# 11Dof_MPU6050_HighAcc.net
KiCad netlist of a schematic drawn in EAGLE
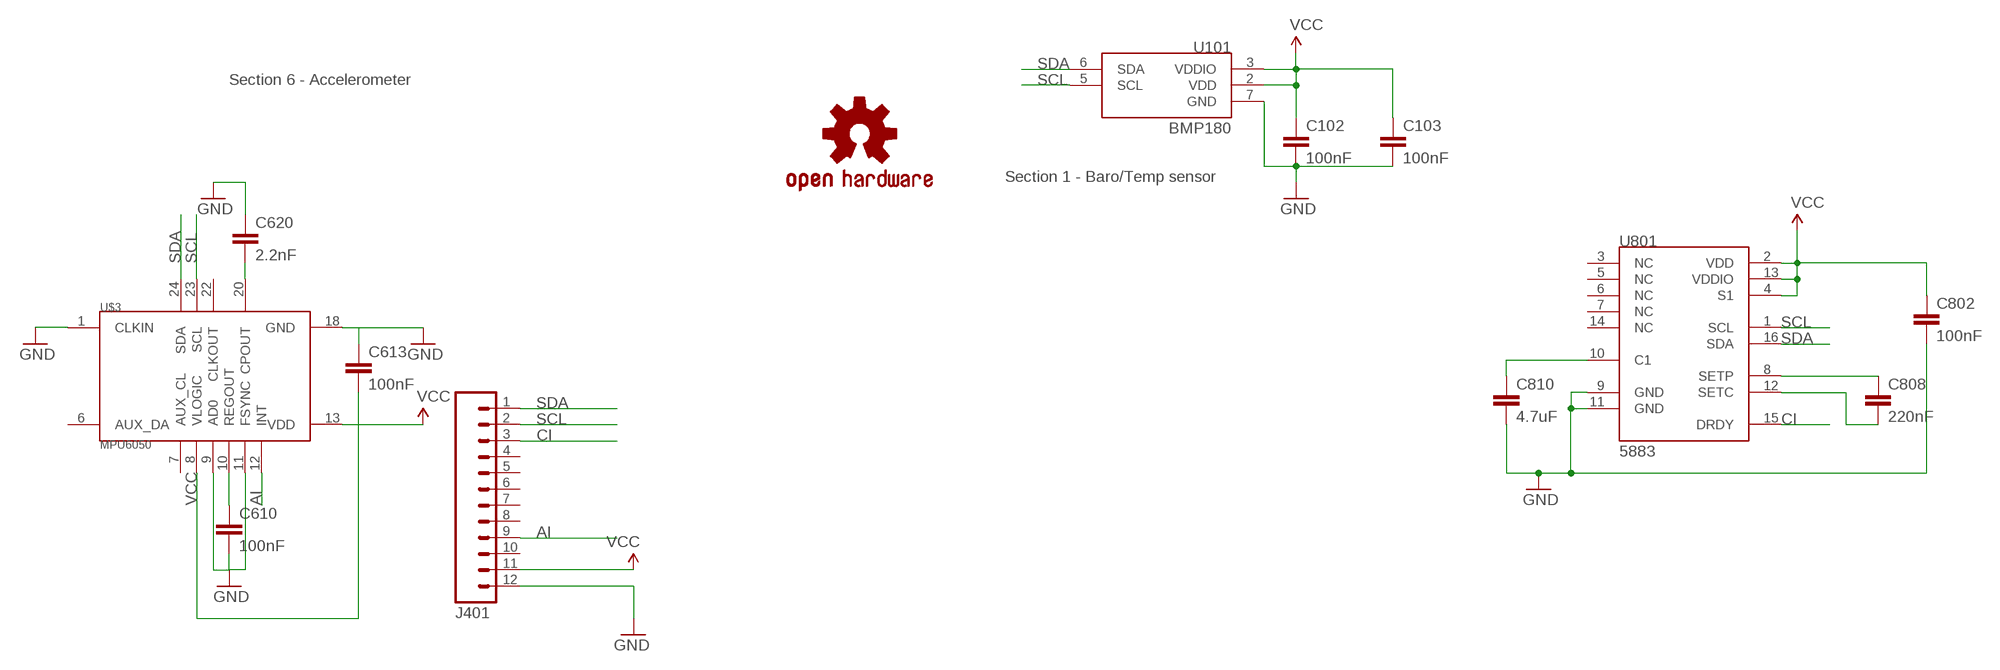
[diagram p0: schematic, sheet 1]

(export (version "E")
  (design (tool "Eeschema 10.0.6"))
  (components
    (comp (ref "C102")
      (value "100nF")
      (footprint "eagle-import:0603-CAP")
      (libsource (lib "eagle-import") (part "CAP0603-CAP"))
    )
    (comp (ref "C103")
      (value "100nF")
      (footprint "eagle-import:0603-CAP")
      (libsource (lib "eagle-import") (part "CAP0603-CAP"))
    )
    (comp (ref "C610")
      (value "100nF")
      (footprint "eagle-import:0603-CAP")
      (libsource (lib "eagle-import") (part "CAP0603-CAP"))
    )
    (comp (ref "C613")
      (value "100nF")
      (footprint "eagle-import:0603-CAP")
      (libsource (lib "eagle-import") (part "CAP0603-CAP"))
    )
    (comp (ref "C620")
      (value "2.2nF")
      (footprint "eagle-import:0603-CAP")
      (libsource (lib "eagle-import") (part "CAP0603-CAP"))
    )
    (comp (ref "C802")
      (value "100nF")
      (footprint "eagle-import:0603-CAP")
      (libsource (lib "eagle-import") (part "CAP0603-CAP"))
    )
    (comp (ref "C808")
      (value "220nF")
      (footprint "eagle-import:0603-CAP")
      (libsource (lib "eagle-import") (part "CAP0603-CAP"))
    )
    (comp (ref "C810")
      (value "4.7uF")
      (footprint "eagle-import:0603-CAP")
      (libsource (lib "eagle-import") (part "CAP0603-CAP"))
    )
    (comp (ref "J401")
      (value "M12PTH")
      (footprint "eagle-import:1X12")
      (libsource (lib "eagle-import") (part "M12PTH"))
    )
    (comp (ref "U$2")
      (value "OSHW-LOGOS")
      (footprint "eagle-import:OSHW-LOGO-S")
      (libsource (lib "eagle-import") (part "OSHW-LOGOS"))
    )
    (comp (ref "U$3")
      (value "MPU6050")
      (footprint "eagle-import:MPU60X0")
      (libsource (lib "eagle-import") (part "MPU6050"))
    )
    (comp (ref "U101")
      (value "BMP180")
      (footprint "eagle-import:BMP180")
      (libsource (lib "eagle-import") (part "BMP180"))
    )
    (comp (ref "U801")
      (value "5883")
      (footprint "eagle-import:16LPCC")
      (libsource (lib "eagle-import") (part "HMC5883LSMD"))
    )
  )
  (nets
    (net (code "1") (name "/AI") (class "Default")
      (node (ref "J401") (pin "9") (pinfunction "9_9") (pintype "passive"))
      (node (ref "U$3") (pin "12") (pinfunction "INT_12") (pintype "output"))
    )
    (net (code "2") (name "/CI") (class "Default")
      (node (ref "J401") (pin "3") (pinfunction "3_3") (pintype "passive"))
      (node (ref "U801") (pin "15") (pinfunction "DRDY_15") (pintype "bidirectional"))
    )
    (net (code "3") (name "/SCL") (class "Default")
      (node (ref "J401") (pin "2") (pinfunction "2_2") (pintype "passive"))
      (node (ref "U$3") (pin "23") (pinfunction "SCL_23") (pintype "bidirectional"))
      (node (ref "U101") (pin "5") (pinfunction "SCL_5") (pintype "input"))
      (node (ref "U801") (pin "1") (pinfunction "SCL_1") (pintype "bidirectional"))
    )
    (net (code "4") (name "/SDA") (class "Default")
      (node (ref "J401") (pin "1") (pinfunction "1_1") (pintype "passive"))
      (node (ref "U$3") (pin "24") (pinfunction "SDA_24") (pintype "bidirectional"))
      (node (ref "U101") (pin "6") (pinfunction "SDA_6") (pintype "bidirectional"))
      (node (ref "U801") (pin "16") (pinfunction "SDA_16") (pintype "bidirectional"))
    )
    (net (code "5") (name "GND") (class "Default")
      (node (ref "C102") (pin "2") (pinfunction "2_2") (pintype "passive"))
      (node (ref "C103") (pin "2") (pinfunction "2_2") (pintype "passive"))
      (node (ref "C610") (pin "2") (pinfunction "2_2") (pintype "passive"))
      (node (ref "C613") (pin "1") (pinfunction "1_1") (pintype "passive"))
      (node (ref "C620") (pin "1") (pinfunction "1_1") (pintype "passive"))
      (node (ref "C802") (pin "2") (pinfunction "2_2") (pintype "passive"))
      (node (ref "C810") (pin "2") (pinfunction "2_2") (pintype "passive"))
      (node (ref "J401") (pin "12") (pinfunction "12_12") (pintype "passive"))
      (node (ref "U$3") (pin "1") (pinfunction "CLKIN_1") (pintype "input"))
      (node (ref "U$3") (pin "11") (pinfunction "FSYNC_11") (pintype "bidirectional"))
      (node (ref "U$3") (pin "18") (pinfunction "GND_18") (pintype "power_in"))
      (node (ref "U$3") (pin "9") (pinfunction "AD0_9") (pintype "output"))
      (node (ref "U101") (pin "7") (pinfunction "GND_7") (pintype "power_in"))
      (node (ref "U801") (pin "11") (pinfunction "GND_11") (pintype "bidirectional"))
      (node (ref "U801") (pin "9") (pinfunction "GND_9") (pintype "bidirectional"))
    )
    (net (code "6") (name "Net-(U$3-CPOUT)") (class "Default")
      (node (ref "C620") (pin "2") (pinfunction "2_2") (pintype "passive"))
      (node (ref "U$3") (pin "20") (pinfunction "CPOUT_20") (pintype "output"))
    )
    (net (code "7") (name "Net-(U$3-REGOUT)") (class "Default")
      (node (ref "C610") (pin "1") (pinfunction "1_1") (pintype "passive"))
      (node (ref "U$3") (pin "10") (pinfunction "REGOUT_10") (pintype "bidirectional"))
    )
    (net (code "8") (name "Net-(U801-C1)") (class "Default")
      (node (ref "C810") (pin "1") (pinfunction "1_1") (pintype "passive"))
      (node (ref "U801") (pin "10") (pinfunction "C1_10") (pintype "bidirectional"))
    )
    (net (code "9") (name "Net-(U801-SETC)") (class "Default")
      (node (ref "C808") (pin "2") (pinfunction "2_2") (pintype "passive"))
      (node (ref "U801") (pin "12") (pinfunction "SETC_12") (pintype "bidirectional"))
    )
    (net (code "10") (name "Net-(U801-SETP)") (class "Default")
      (node (ref "C808") (pin "1") (pinfunction "1_1") (pintype "passive"))
      (node (ref "U801") (pin "8") (pinfunction "SETP_8") (pintype "bidirectional"))
    )
    (net (code "11") (name "VCC") (class "Default")
      (node (ref "C102") (pin "1") (pinfunction "1_1") (pintype "passive"))
      (node (ref "C103") (pin "1") (pinfunction "1_1") (pintype "passive"))
      (node (ref "C613") (pin "2") (pinfunction "2_2") (pintype "passive"))
      (node (ref "C802") (pin "1") (pinfunction "1_1") (pintype "passive"))
      (node (ref "J401") (pin "11") (pinfunction "11_11") (pintype "passive"))
      (node (ref "U$3") (pin "13") (pinfunction "VDD_13") (pintype "power_in"))
      (node (ref "U$3") (pin "8") (pinfunction "VLOGIC_8") (pintype "bidirectional"))
      (node (ref "U101") (pin "2") (pinfunction "VDD_2") (pintype "power_in"))
      (node (ref "U101") (pin "3") (pinfunction "VDDIO_3") (pintype "power_in"))
      (node (ref "U801") (pin "13") (pinfunction "VDDIO_13") (pintype "bidirectional"))
      (node (ref "U801") (pin "2") (pinfunction "VDD_2") (pintype "bidirectional"))
      (node (ref "U801") (pin "4") (pinfunction "S1_4") (pintype "bidirectional"))
    )
    (net (code "12") (name "unconnected-(J401-Pad4)") (class "Default")
      (node (ref "J401") (pin "4") (pinfunction "4_4") (pintype "passive"))
    )
    (net (code "13") (name "unconnected-(J401-Pad5)") (class "Default")
      (node (ref "J401") (pin "5") (pinfunction "5_5") (pintype "passive"))
    )
    (net (code "14") (name "unconnected-(J401-Pad6)") (class "Default")
      (node (ref "J401") (pin "6") (pinfunction "6_6") (pintype "passive"))
    )
    (net (code "15") (name "unconnected-(J401-Pad7)") (class "Default")
      (node (ref "J401") (pin "7") (pinfunction "7_7") (pintype "passive"))
    )
    (net (code "16") (name "unconnected-(J401-Pad8)") (class "Default")
      (node (ref "J401") (pin "8") (pinfunction "8_8") (pintype "passive"))
    )
    (net (code "17") (name "unconnected-(J401-Pad10)") (class "Default")
      (node (ref "J401") (pin "10") (pinfunction "10_10") (pintype "passive"))
    )
    (net (code "18") (name "unconnected-(U$3-AUX_CL-Pad7)") (class "Default")
      (node (ref "U$3") (pin "7") (pinfunction "AUX_CL_7") (pintype "bidirectional"))
    )
    (net (code "19") (name "unconnected-(U$3-AUX_DA-Pad6)") (class "Default")
      (node (ref "U$3") (pin "6") (pinfunction "AUX_DA_6") (pintype "bidirectional"))
    )
    (net (code "20") (name "unconnected-(U$3-CLKOUT-Pad22)") (class "Default")
      (node (ref "U$3") (pin "22") (pinfunction "CLKOUT_22") (pintype "bidirectional"))
    )
    (net (code "21") (name "unconnected-(U801-NC-Pad3)") (class "Default")
      (node (ref "U801") (pin "3") (pinfunction "NC_3") (pintype "bidirectional"))
    )
    (net (code "22") (name "unconnected-(U801-NC-Pad5)") (class "Default")
      (node (ref "U801") (pin "5") (pinfunction "NC_5") (pintype "bidirectional"))
    )
    (net (code "23") (name "unconnected-(U801-NC-Pad6)") (class "Default")
      (node (ref "U801") (pin "6") (pinfunction "NC_6") (pintype "bidirectional"))
    )
    (net (code "24") (name "unconnected-(U801-NC-Pad7)") (class "Default")
      (node (ref "U801") (pin "7") (pinfunction "NC_7") (pintype "bidirectional"))
    )
    (net (code "25") (name "unconnected-(U801-NC-Pad14)") (class "Default")
      (node (ref "U801") (pin "14") (pinfunction "NC_14") (pintype "bidirectional"))
    )
  )
)
